# NIR-Spec-Motherboard-SCH_SH3__02.net
KiCad netlist of a schematic drawn in Altium Designer
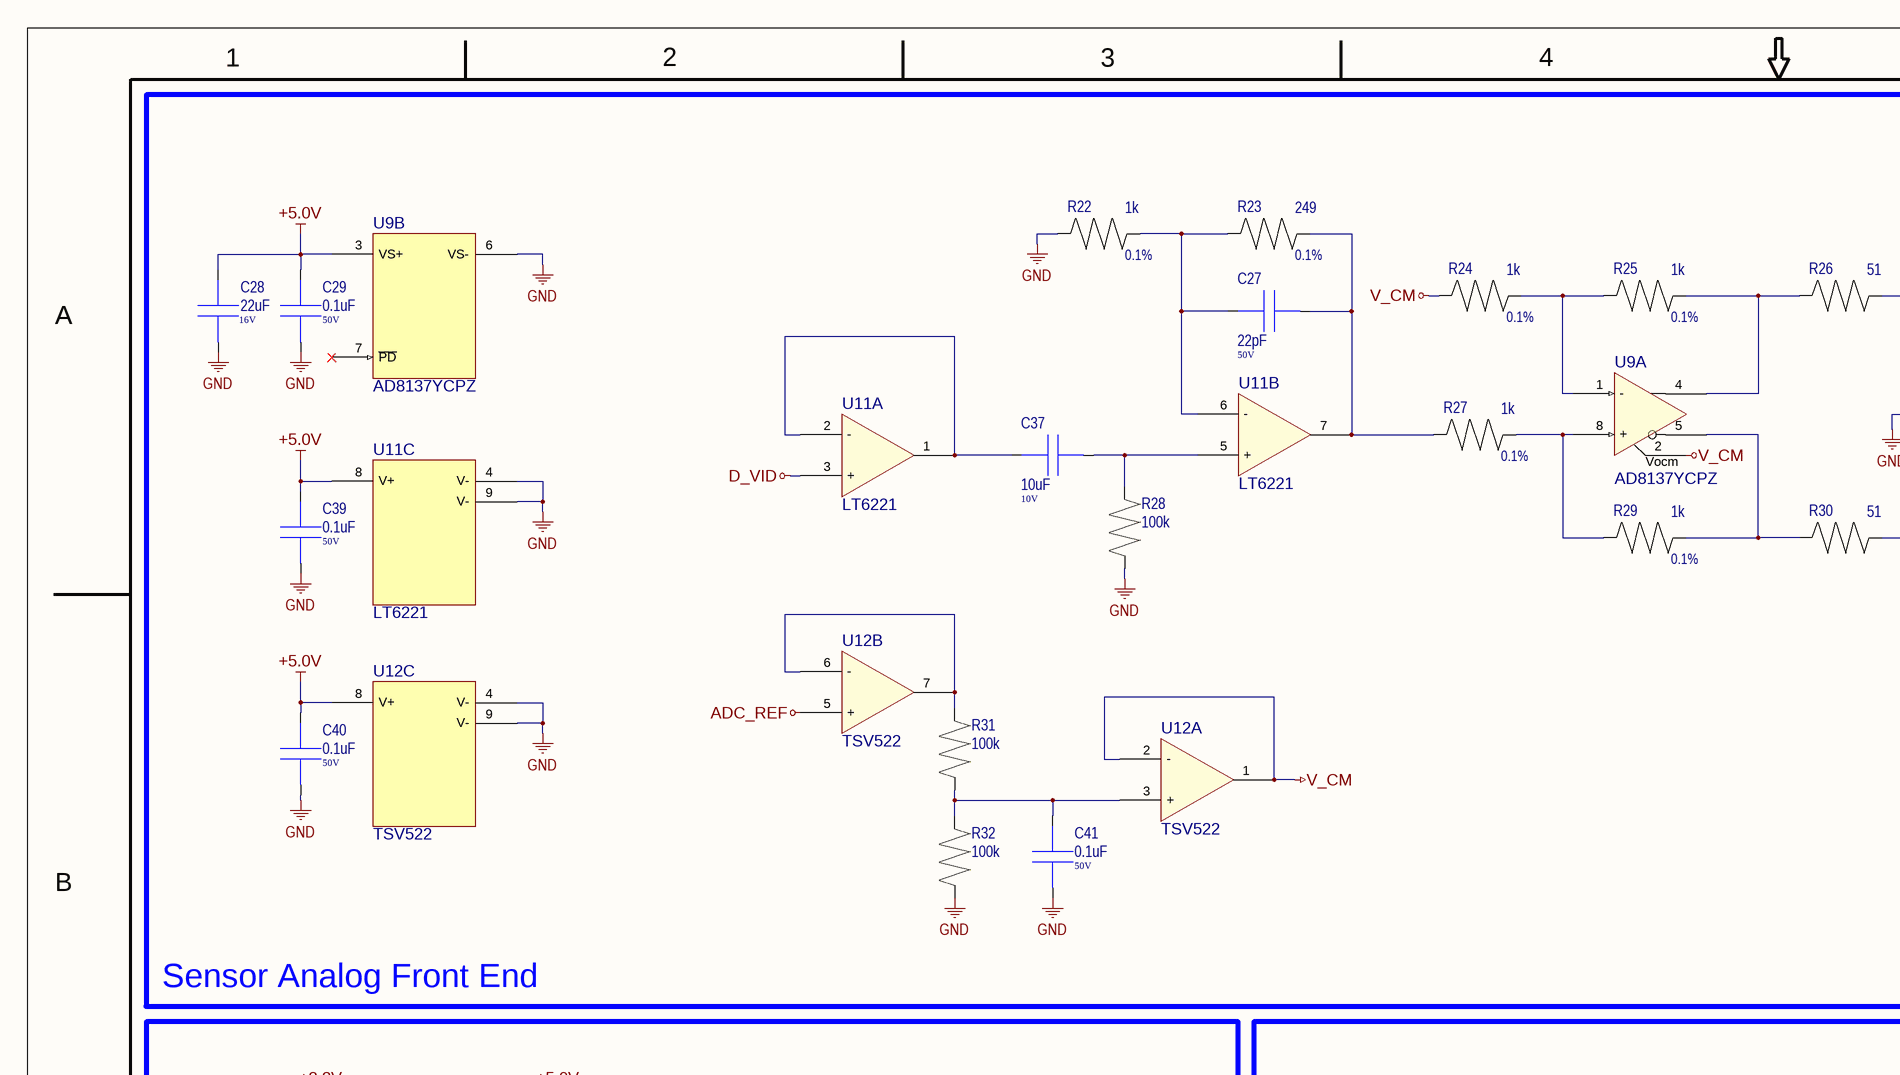
[diagram p0: NIR-Spec-Motherboard-SCH_SH3_(02).SchDoc, top left]
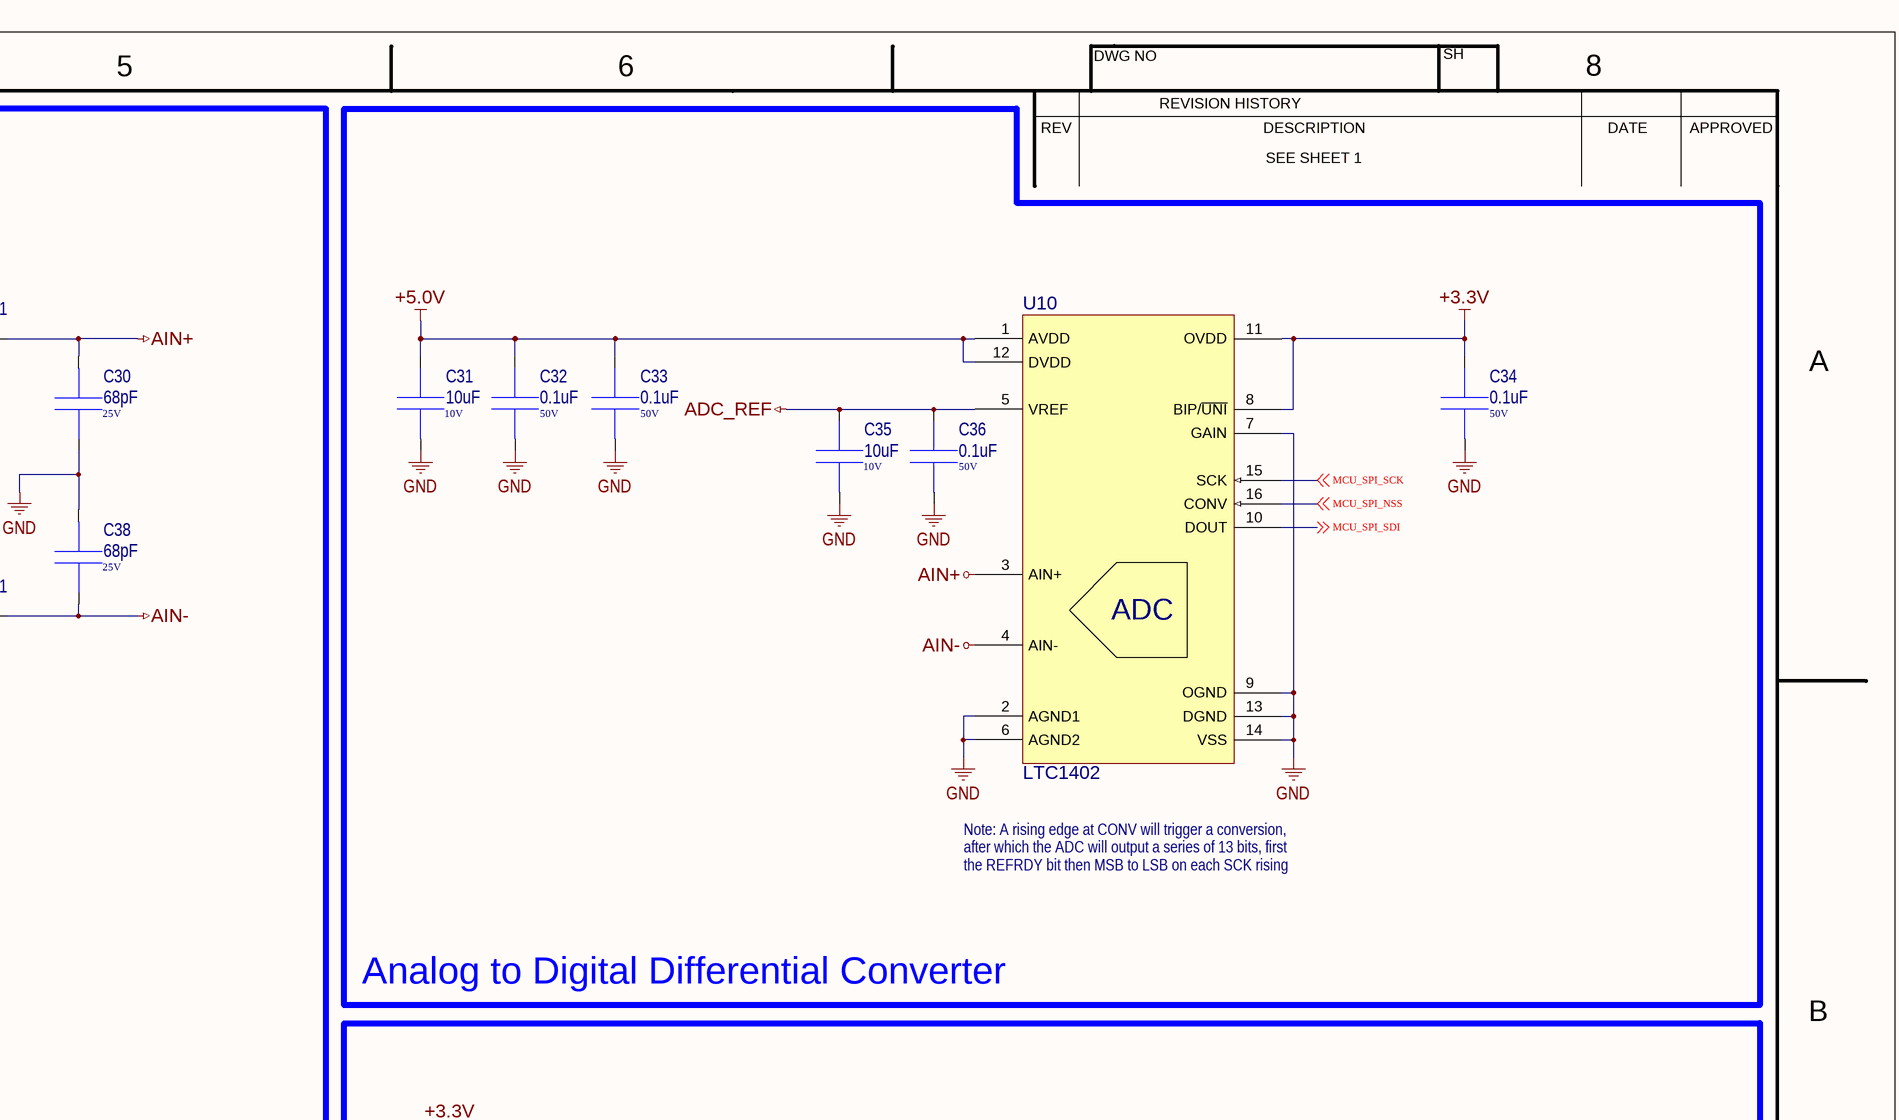
[diagram p1: NIR-Spec-Motherboard-SCH_SH3_(02).SchDoc, top right]
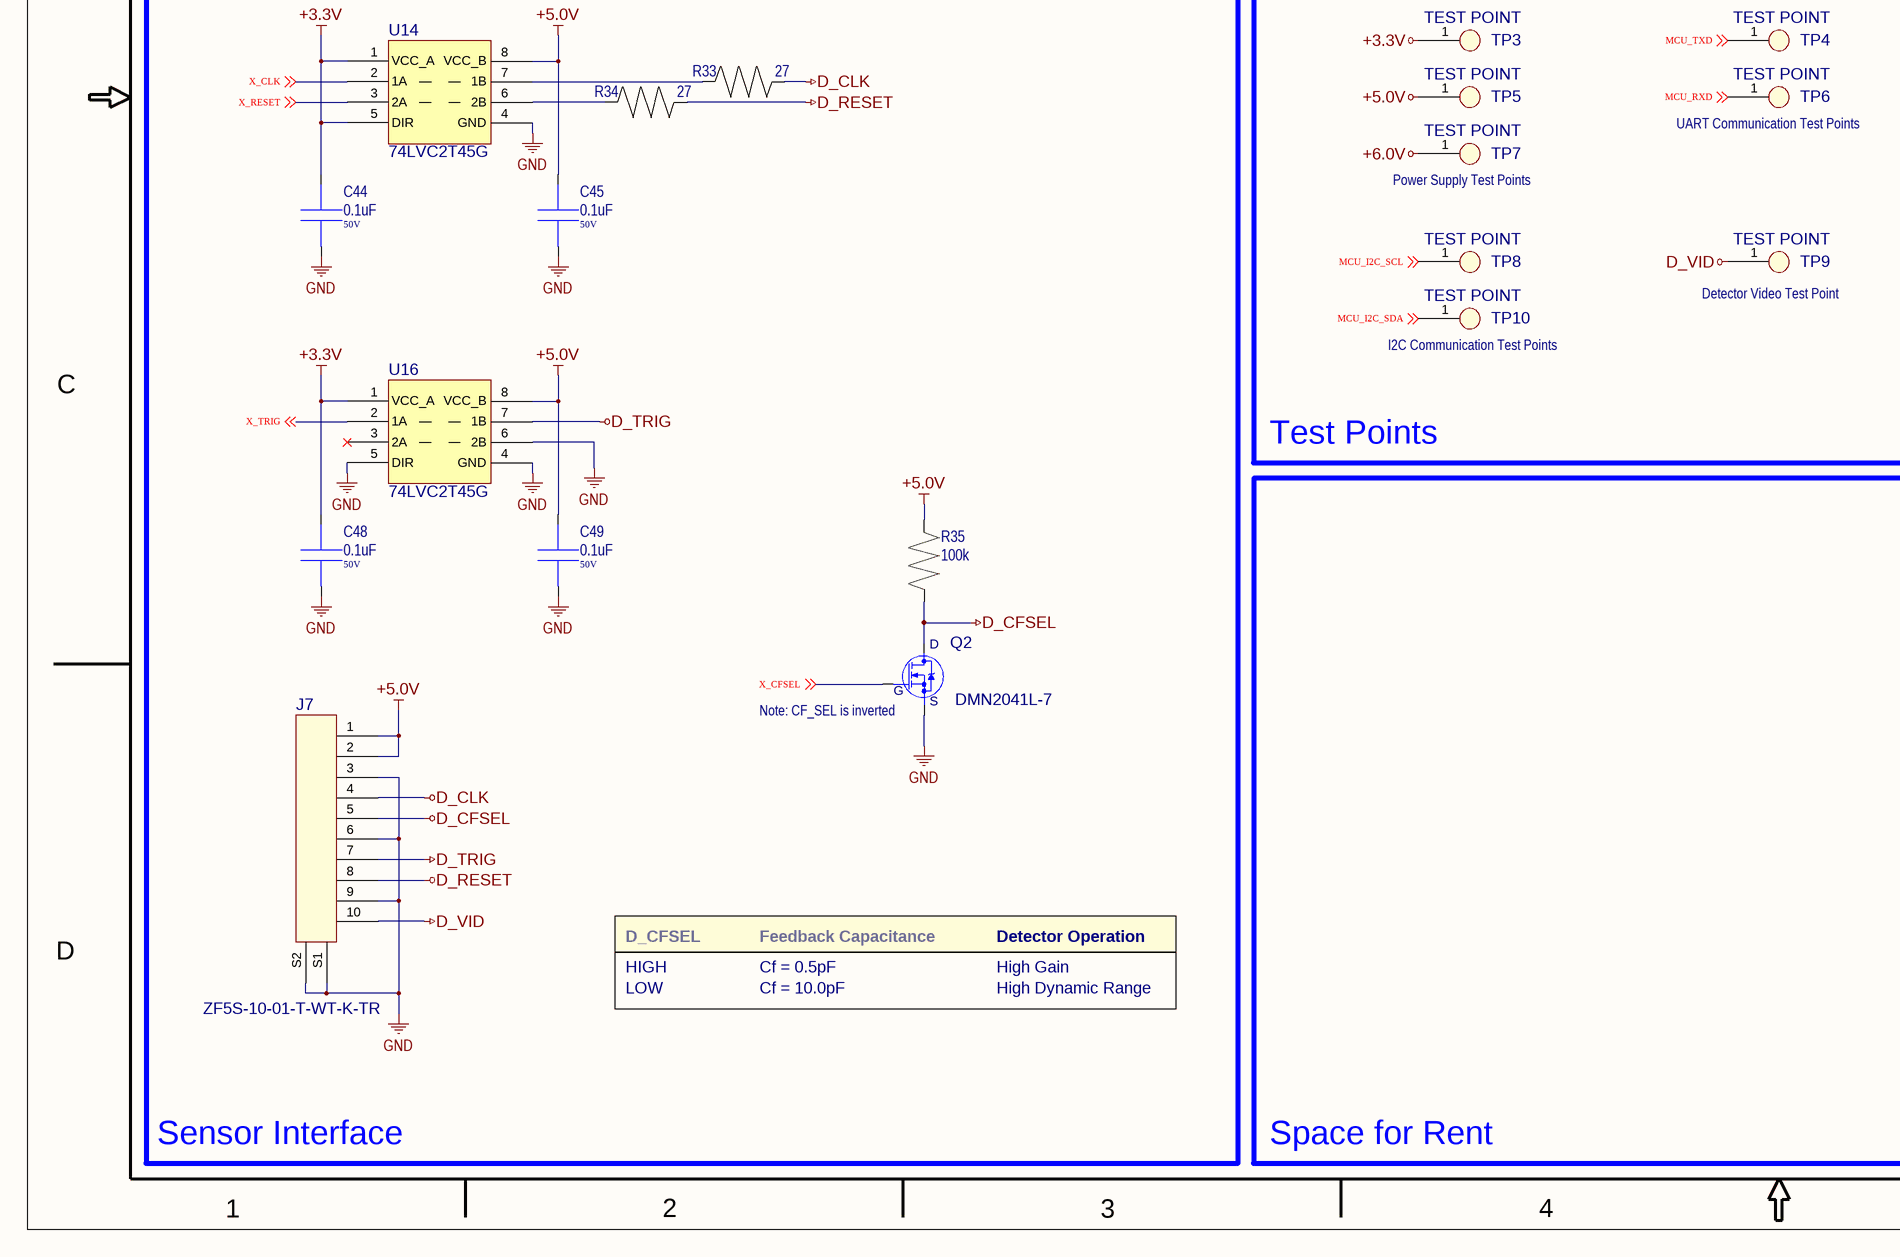
[diagram p2: NIR-Spec-Motherboard-SCH_SH3_(02).SchDoc, bottom left]
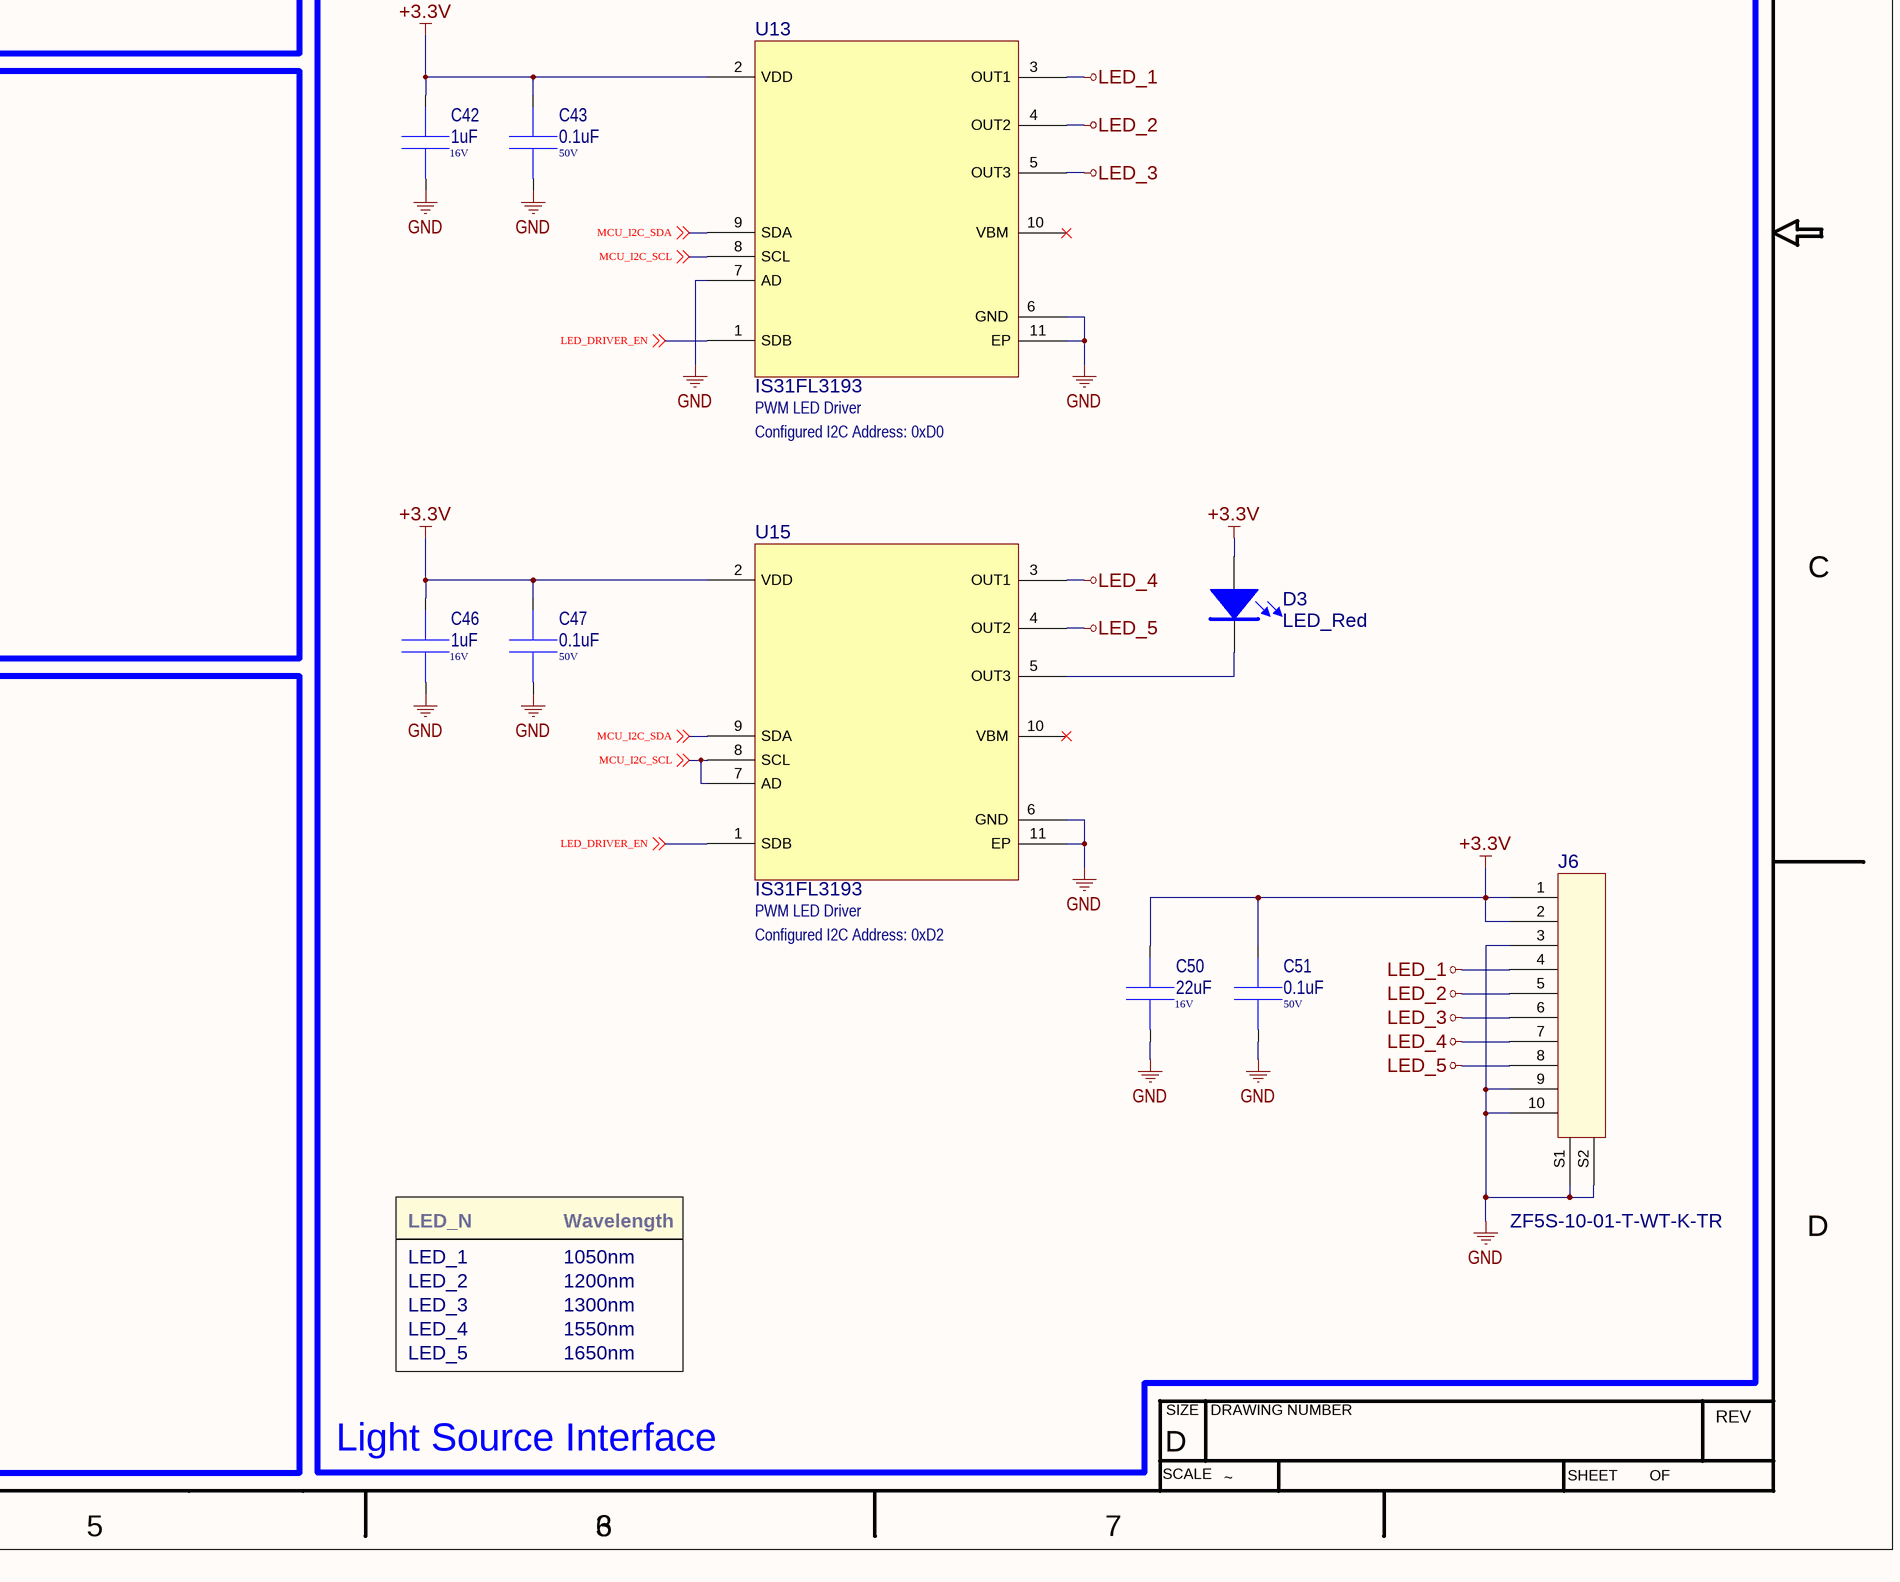
[diagram p3: NIR-Spec-Motherboard-SCH_SH3_(02).SchDoc, bottom right]

(export (version "E")
  (design (tool "Eeschema 10.0.6"))
  (components
    (comp (ref "C27")
      (value "22pF")
      (footprint "0603")
      (description "CAP CER 22PF NP0 50V 0603")
      (fields
        (field (name "PART NUMBER") "VJ0603A220KXAAC")
        (field (name "MANUFACTURER") "Vishay")
        (field (name "VOLTAGE") "50V")
      )
      (libsource (lib "CAPACITORS") (part "CAP"))
    )
    (comp (ref "C28")
      (value "22uF")
      (footprint "0805")
      (description "CAP CER 22UF 16V X5R 0805")
      (fields
        (field (name "PART NUMBER") "CL21A226MOCLRNC")
        (field (name "MANUFACTURER") "Samsung Electro-Mechanics")
        (field (name "VOLTAGE") "16V")
      )
      (libsource (lib "CAPACITORS") (part "CAP"))
    )
    (comp (ref "C29")
      (value "0.1uF")
      (footprint "0603")
      (description "CAP CER 0.1UF 50V X7R 0603")
      (fields
        (field (name "PART NUMBER") "C0603C104K5RAC3121")
        (field (name "MANUFACTURER") "KEMET")
        (field (name "VOLTAGE") "50V")
      )
      (libsource (lib "CAPACITORS") (part "CAP"))
    )
    (comp (ref "C30")
      (value "68pF")
      (footprint "0603")
      (description "CAP CER 68PF 25V NP0 0603")
      (fields
        (field (name "PART NUMBER") "VJ0603A680KXXPW1BC")
        (field (name "MANUFACTURER") "Vishay")
        (field (name "VOLTAGE") "25V")
      )
      (libsource (lib "CAPACITORS") (part "CAP"))
    )
    (comp (ref "C31")
      (value "10uF")
      (footprint "0603")
      (description "CAP CER 10UF 10V X6S 0603")
      (fields
        (field (name "PART NUMBER") "GRM188C81A106MA73D")
        (field (name "MANUFACTURER") "Murata Electronics")
        (field (name "VOLTAGE") "10V")
      )
      (libsource (lib "CAPACITORS") (part "CAP"))
    )
    (comp (ref "C32")
      (value "0.1uF")
      (footprint "0603")
      (description "CAP CER 0.1UF 50V X7R 0603")
      (fields
        (field (name "PART NUMBER") "C0603C104K5RAC3121")
        (field (name "MANUFACTURER") "KEMET")
        (field (name "VOLTAGE") "50V")
      )
      (libsource (lib "CAPACITORS") (part "CAP"))
    )
    (comp (ref "C33")
      (value "0.1uF")
      (footprint "0603")
      (description "CAP CER 0.1UF 50V X7R 0603")
      (fields
        (field (name "PART NUMBER") "C0603C104K5RAC3121")
        (field (name "MANUFACTURER") "KEMET")
        (field (name "VOLTAGE") "50V")
      )
      (libsource (lib "CAPACITORS") (part "CAP"))
    )
    (comp (ref "C34")
      (value "0.1uF")
      (footprint "0603")
      (description "CAP CER 0.1UF 50V X7R 0603")
      (fields
        (field (name "PART NUMBER") "C0603C104K5RAC3121")
        (field (name "MANUFACTURER") "KEMET")
        (field (name "VOLTAGE") "50V")
      )
      (libsource (lib "CAPACITORS") (part "CAP"))
    )
    (comp (ref "C35")
      (value "10uF")
      (footprint "0603")
      (description "CAP CER 10UF 10V X6S 0603")
      (fields
        (field (name "PART NUMBER") "GRM188C81A106MA73D")
        (field (name "MANUFACTURER") "Murata Electronics")
        (field (name "VOLTAGE") "10V")
      )
      (libsource (lib "CAPACITORS") (part "CAP"))
    )
    (comp (ref "C36")
      (value "0.1uF")
      (footprint "0603")
      (description "CAP CER 0.1UF 50V X7R 0603")
      (fields
        (field (name "PART NUMBER") "C0603C104K5RAC3121")
        (field (name "MANUFACTURER") "KEMET")
        (field (name "VOLTAGE") "50V")
      )
      (libsource (lib "CAPACITORS") (part "CAP"))
    )
    (comp (ref "C37")
      (value "10uF")
      (footprint "0603")
      (description "CAP CER 10UF 10V X6S 0603")
      (fields
        (field (name "PART NUMBER") "GRM188C81A106MA73D")
        (field (name "MANUFACTURER") "Murata Electronics")
        (field (name "VOLTAGE") "10V")
      )
      (libsource (lib "CAPACITORS") (part "CAP"))
    )
    (comp (ref "C38")
      (value "68pF")
      (footprint "0603")
      (description "CAP CER 68PF 25V NP0 0603")
      (fields
        (field (name "PART NUMBER") "VJ0603A680KXXPW1BC")
        (field (name "MANUFACTURER") "Vishay")
        (field (name "VOLTAGE") "25V")
      )
      (libsource (lib "CAPACITORS") (part "CAP"))
    )
    (comp (ref "C39")
      (value "0.1uF")
      (footprint "0603")
      (description "CAP CER 0.1UF 50V X7R 0603")
      (fields
        (field (name "PART NUMBER") "C0603C104K5RAC3121")
        (field (name "MANUFACTURER") "KEMET")
        (field (name "VOLTAGE") "50V")
      )
      (libsource (lib "CAPACITORS") (part "CAP"))
    )
    (comp (ref "C40")
      (value "0.1uF")
      (footprint "0603")
      (description "CAP CER 0.1UF 50V X7R 0603")
      (fields
        (field (name "PART NUMBER") "C0603C104K5RAC3121")
        (field (name "MANUFACTURER") "KEMET")
        (field (name "VOLTAGE") "50V")
      )
      (libsource (lib "CAPACITORS") (part "CAP"))
    )
    (comp (ref "C41")
      (value "0.1uF")
      (footprint "0603")
      (description "CAP CER 0.1UF 50V X7R 0603")
      (fields
        (field (name "PART NUMBER") "C0603C104K5RAC3121")
        (field (name "MANUFACTURER") "KEMET")
        (field (name "VOLTAGE") "50V")
      )
      (libsource (lib "CAPACITORS") (part "CAP"))
    )
    (comp (ref "C42")
      (value "1uF")
      (footprint "0603")
      (description "CAP CER 1UF 10V X5R 0603")
      (fields
        (field (name "PART NUMBER") "GRM188R61C105KA12J")
        (field (name "MANUFACTURER") "Murata Electronics")
        (field (name "VOLTAGE") "16V")
      )
      (libsource (lib "CAPACITORS") (part "CAP"))
    )
    (comp (ref "C43")
      (value "0.1uF")
      (footprint "0603")
      (description "CAP CER 0.1UF 50V X7R 0603")
      (fields
        (field (name "PART NUMBER") "C0603C104K5RAC3121")
        (field (name "MANUFACTURER") "KEMET")
        (field (name "VOLTAGE") "50V")
      )
      (libsource (lib "CAPACITORS") (part "CAP"))
    )
    (comp (ref "C44")
      (value "0.1uF")
      (footprint "0603")
      (description "CAP CER 0.1UF 50V X7R 0603")
      (fields
        (field (name "PART NUMBER") "C0603C104K5RAC3121")
        (field (name "MANUFACTURER") "KEMET")
        (field (name "VOLTAGE") "50V")
      )
      (libsource (lib "CAPACITORS") (part "CAP"))
    )
    (comp (ref "C45")
      (value "0.1uF")
      (footprint "0603")
      (description "CAP CER 0.1UF 50V X7R 0603")
      (fields
        (field (name "PART NUMBER") "C0603C104K5RAC3121")
        (field (name "MANUFACTURER") "KEMET")
        (field (name "VOLTAGE") "50V")
      )
      (libsource (lib "CAPACITORS") (part "CAP"))
    )
    (comp (ref "C46")
      (value "1uF")
      (footprint "0603")
      (description "CAP CER 1UF 10V X5R 0603")
      (fields
        (field (name "PART NUMBER") "GRM188R61C105KA12J")
        (field (name "MANUFACTURER") "Murata Electronics")
        (field (name "VOLTAGE") "16V")
      )
      (libsource (lib "CAPACITORS") (part "CAP"))
    )
    (comp (ref "C47")
      (value "0.1uF")
      (footprint "0603")
      (description "CAP CER 0.1UF 50V X7R 0603")
      (fields
        (field (name "PART NUMBER") "C0603C104K5RAC3121")
        (field (name "MANUFACTURER") "KEMET")
        (field (name "VOLTAGE") "50V")
      )
      (libsource (lib "CAPACITORS") (part "CAP"))
    )
    (comp (ref "C48")
      (value "0.1uF")
      (footprint "0603")
      (description "CAP CER 0.1UF 50V X7R 0603")
      (fields
        (field (name "PART NUMBER") "C0603C104K5RAC3121")
        (field (name "MANUFACTURER") "KEMET")
        (field (name "VOLTAGE") "50V")
      )
      (libsource (lib "CAPACITORS") (part "CAP"))
    )
    (comp (ref "C49")
      (value "0.1uF")
      (footprint "0603")
      (description "CAP CER 0.1UF 50V X7R 0603")
      (fields
        (field (name "PART NUMBER") "C0603C104K5RAC3121")
        (field (name "MANUFACTURER") "KEMET")
        (field (name "VOLTAGE") "50V")
      )
      (libsource (lib "CAPACITORS") (part "CAP"))
    )
    (comp (ref "C50")
      (value "22uF")
      (footprint "0805")
      (description "CAP CER 22UF 16V X5R 0805")
      (fields
        (field (name "PART NUMBER") "CL21A226MOCLRNC")
        (field (name "MANUFACTURER") "Samsung Electro-Mechanics")
        (field (name "VOLTAGE") "16V")
      )
      (libsource (lib "CAPACITORS") (part "CAP"))
    )
    (comp (ref "C51")
      (value "0.1uF")
      (footprint "0603")
      (description "CAP CER 0.1UF 50V X7R 0603")
      (fields
        (field (name "PART NUMBER") "C0603C104K5RAC3121")
        (field (name "MANUFACTURER") "KEMET")
        (field (name "VOLTAGE") "50V")
      )
      (libsource (lib "CAPACITORS") (part "CAP"))
    )
    (comp (ref "D3")
      (value "LED_Red")
      (footprint "0603_LED_Red")
      (description "Standard LEDs - SMD HE Red 645 nm Water Clear")
      (fields (field (name "PART NUMBER") "SM0603HCL") (field (name "MANUFACTURER") "Bivar"))
      (libsource (lib "SEMICONDUCTORS") (part "LED_Red"))
    )
    (comp (ref "J6")
      (value "ZF5S-10-01-T-WT-K-TR")
      (footprint "ZF5S-10-01-T-WT-K-TR")
      (fields (field (name "MANUFACTURER") "Samtec"))
      (libsource (lib "ZF5S-10-01-T-WT-K-TR") (part "ZF5S-10-01-T-WT-K-TR"))
    )
    (comp (ref "J7")
      (value "ZF5S-10-01-T-WT-K-TR")
      (footprint "ZF5S-10-01-T-WT-K-TR")
      (fields (field (name "MANUFACTURER") "Samtec"))
      (libsource (lib "") (part "ZF5S-10-01-T-WT-K-TR_1"))
    )
    (comp (ref "Q2")
      (value "DMN2041L-7")
      (footprint "SOT-23")
      (description "MOSFET, N CH, 3-PIN")
      (fields (field (name "MANUFACTURER") "Diodes Incorporated"))
      (libsource (lib "SEMICONDUCTORS") (part "MOSFET_N"))
    )
    (comp (ref "R22")
      (value "1k")
      (footprint "0603")
      (description "Thin Film Resistors - SMD CPF A 0603 1K0 0.1% 25PPM")
      (fields (field (name "PART NUMBER") "CPF-A-0603B1K0E") (field (name "MANUFACTURER") "TE Connectivity"))
      (libsource (lib "RESISTORS") (part "RES"))
    )
    (comp (ref "R23")
      (value "249")
      (footprint "0603")
      (description "Thin Film Resistors - SMD 0603 249ohms 25ppm 0.5%")
      (fields (field (name "PART NUMBER") "ERA-3AED2490V") (field (name "MANUFACTURER") "Panasonic"))
      (libsource (lib "RESISTORS") (part "RES"))
    )
    (comp (ref "R24")
      (value "1k")
      (footprint "0603")
      (description "Thin Film Resistors - SMD CPF A 0603 1K0 0.1% 25PPM")
      (fields (field (name "PART NUMBER") "CPF-A-0603B1K0E") (field (name "MANUFACTURER") "TE Connectivity"))
      (libsource (lib "RESISTORS") (part "RES"))
    )
    (comp (ref "R25")
      (value "1k")
      (footprint "0603")
      (description "Thin Film Resistors - SMD CPF A 0603 1K0 0.1% 25PPM")
      (fields (field (name "PART NUMBER") "CPF-A-0603B1K0E") (field (name "MANUFACTURER") "TE Connectivity"))
      (libsource (lib "RESISTORS") (part "RES"))
    )
    (comp (ref "R26")
      (value "51")
      (footprint "0603")
      (description "Thin Film Resistors - SMD .1W 51ohm 1% 0603")
      (fields (field (name "PART NUMBER") "MCT06030C5109FP500") (field (name "MANUFACTURER") "Vishay"))
      (libsource (lib "RESISTORS") (part "RES"))
    )
    (comp (ref "R27")
      (value "1k")
      (footprint "0603")
      (description "Thin Film Resistors - SMD CPF A 0603 1K0 0.1% 25PPM")
      (fields (field (name "PART NUMBER") "CPF-A-0603B1K0E") (field (name "MANUFACTURER") "TE Connectivity"))
      (libsource (lib "RESISTORS") (part "RES"))
    )
    (comp (ref "R28")
      (value "100k")
      (footprint "0603")
      (description "Thick Film Resistors - SMD 0.33W 100Kohms 5%")
      (fields (field (name "PART NUMBER") "CRCW0603100KJNEAHP") (field (name "MANUFACTURER") "Vishay"))
      (libsource (lib "RESISTORS") (part "RES"))
    )
    (comp (ref "R29")
      (value "1k")
      (footprint "0603")
      (description "Thin Film Resistors - SMD CPF A 0603 1K0 0.1% 25PPM")
      (fields (field (name "PART NUMBER") "CPF-A-0603B1K0E") (field (name "MANUFACTURER") "TE Connectivity"))
      (libsource (lib "RESISTORS") (part "RES"))
    )
    (comp (ref "R30")
      (value "51")
      (footprint "0603")
      (description "Thin Film Resistors - SMD .1W 51ohm 1% 0603")
      (fields (field (name "PART NUMBER") "MCT06030C5109FP500") (field (name "MANUFACTURER") "Vishay"))
      (libsource (lib "RESISTORS") (part "RES"))
    )
    (comp (ref "R31")
      (value "100k")
      (footprint "0603")
      (description "Thick Film Resistors - SMD 0.33W 100Kohms 5%")
      (fields (field (name "PART NUMBER") "CRCW0603100KJNEAHP") (field (name "MANUFACTURER") "Vishay"))
      (libsource (lib "RESISTORS") (part "RES"))
    )
    (comp (ref "R32")
      (value "100k")
      (footprint "0603")
      (description "Thick Film Resistors - SMD 0.33W 100Kohms 5%")
      (fields (field (name "PART NUMBER") "CRCW0603100KJNEAHP") (field (name "MANUFACTURER") "Vishay"))
      (libsource (lib "RESISTORS") (part "RES"))
    )
    (comp (ref "R33")
      (value "27")
      (footprint "0603")
      (description "Thin Film Resistors - SMD 0603 27ohms 50ppm 0.5%")
      (fields (field (name "PART NUMBER") "ERA-3AHD270V") (field (name "MANUFACTURER") "Panasonic"))
      (libsource (lib "RESISTORS") (part "RES"))
    )
    (comp (ref "R34")
      (value "27")
      (footprint "0603")
      (description "Thin Film Resistors - SMD 0603 27ohms 50ppm 0.5%")
      (fields (field (name "PART NUMBER") "ERA-3AHD270V") (field (name "MANUFACTURER") "Panasonic"))
      (libsource (lib "RESISTORS") (part "RES"))
    )
    (comp (ref "R35")
      (value "100k")
      (footprint "0603")
      (description "Thick Film Resistors - SMD 0.33W 100Kohms 5%")
      (fields (field (name "PART NUMBER") "CRCW0603100KJNEAHP") (field (name "MANUFACTURER") "Vishay"))
      (libsource (lib "RESISTORS") (part "RES"))
    )
    (comp (ref "TP3")
      (value "TEST POINT")
      (footprint "30x40 TP")
      (libsource (lib "TestPoint") (part "TEST POINT"))
    )
    (comp (ref "TP4")
      (value "TEST POINT")
      (footprint "30x40 TP")
      (libsource (lib "TestPoint") (part "TEST POINT"))
    )
    (comp (ref "TP5")
      (value "TEST POINT")
      (footprint "30x40 TP")
      (libsource (lib "TestPoint") (part "TEST POINT"))
    )
    (comp (ref "TP6")
      (value "TEST POINT")
      (footprint "30x40 TP")
      (libsource (lib "TestPoint") (part "TEST POINT"))
    )
    (comp (ref "TP7")
      (value "TEST POINT")
      (footprint "30x40 TP")
      (libsource (lib "TestPoint") (part "TEST POINT"))
    )
    (comp (ref "TP8")
      (value "TEST POINT")
      (footprint "30x40 TP")
      (libsource (lib "TestPoint") (part "TEST POINT"))
    )
    (comp (ref "TP9")
      (value "TEST POINT")
      (footprint "30x40 TP")
      (libsource (lib "TestPoint") (part "TEST POINT"))
    )
    (comp (ref "TP10")
      (value "TEST POINT")
      (footprint "30x40 TP")
      (libsource (lib "TestPoint") (part "TEST POINT"))
    )
    (comp (ref "U9")
      (value "AD8137YCPZ")
      (footprint "SOIC_8")
      (description "IC OPAMP DIFF 110MHZ RRO 8SOIC")
      (fields (field (name "MANUFACTURER") "Analog Devices"))
      (libsource (lib "Op_Amps") (part "AD8137YRZ-Rxxxx"))
    )
    (comp (ref "U10")
      (value "LTC1402")
      (footprint "LTC1402")
      (description "12 Bit Analog to Digital Converter 1 Input 1 SAR 16-SSOP")
      (fields (field (name "MANUFACTURER") "Linear Technology"))
      (libsource (lib "LTC1402") (part "LTC1402"))
    )
    (comp (ref "U11")
      (value "LT6221")
      (footprint "DFN-8(3x3)")
      (description "IC OPAMP GP 2 CIRCUIT 8DFN")
      (fields
        (field (name "MANUFACTURER") "Linear Technology")
        (field (name "PART NUMBER") "LT6221xDD#TRPBF")
      )
      (libsource (lib "Op_Amps") (part "LT6221xDD#TRPBF"))
    )
    (comp (ref "U12")
      (value "TSV522")
      (footprint "DFN-8 2x2")
      (description "IC CMOS 2 CIRCUIT 8DFN")
      (fields (field (name "MANUFACTURER") "ST Microelectronics") (field (name "PART NUMBER") "TSV522IQ2T"))
      (libsource (lib "TSV522") (part "TSV522"))
    )
    (comp (ref "U13")
      (value "IS31FL3193")
      (footprint "DFN-10")
      (description "IC LED DRIVER LINEAR 42MA 10DFN")
      (fields
        (field (name "MANUFACTURER") "Lumissil Microsystems")
        (field (name "PART NUMBER") "IS31FL3193-DLS2-TR")
      )
      (libsource (lib "IS31FL3193") (part "IS31FL3193"))
    )
    (comp (ref "U14")
      (value "74LVC2T45G")
      (footprint "SOT-765")
      (description "IC TRNSLTR BIDIRECTIONAL 8XSON")
      (fields (field (name "MANUFACTURER") "Nexperia USA") (field (name "PART NUMBER") "74LVC2T45DC,115"))
      (libsource (lib "Logic") (part "74LVC2T45G"))
    )
    (comp (ref "U15")
      (value "IS31FL3193")
      (footprint "DFN-10")
      (description "IC LED DRIVER LINEAR 42MA 10DFN")
      (fields
        (field (name "MANUFACTURER") "Lumissil Microsystems")
        (field (name "PART NUMBER") "IS31FL3193-DLS2-TR")
      )
      (libsource (lib "IS31FL3193") (part "IS31FL3193"))
    )
    (comp (ref "U16")
      (value "74LVC2T45G")
      (footprint "SOT-765")
      (description "IC TRNSLTR BIDIRECTIONAL 8XSON")
      (fields (field (name "MANUFACTURER") "Nexperia USA") (field (name "PART NUMBER") "74LVC2T45DC,115"))
      (libsource (lib "Logic") (part "74LVC2T45G"))
    )
  )
  (nets
    (net (code "1") (name "+3.3V") (class "Default")
      (node (ref "C34") (pin "2") (pinfunction "2_2") (pintype "passive"))
      (node (ref "C42") (pin "2") (pinfunction "2_2") (pintype "passive"))
      (node (ref "C43") (pin "2") (pinfunction "2_2") (pintype "passive"))
      (node (ref "C44") (pin "2") (pinfunction "2_2") (pintype "passive"))
      (node (ref "C46") (pin "2") (pinfunction "2_2") (pintype "passive"))
      (node (ref "C47") (pin "2") (pinfunction "2_2") (pintype "passive"))
      (node (ref "C48") (pin "2") (pinfunction "2_2") (pintype "passive"))
      (node (ref "C50") (pin "2") (pinfunction "2_2") (pintype "passive"))
      (node (ref "C51") (pin "2") (pinfunction "2_2") (pintype "passive"))
      (node (ref "D3") (pin "1") (pinfunction "A_1") (pintype "passive"))
      (node (ref "J6") (pin "1") (pinfunction "1_1") (pintype "passive"))
      (node (ref "J6") (pin "2") (pinfunction "2_2") (pintype "passive"))
      (node (ref "TP3") (pin "1") (pinfunction "1_1") (pintype "passive"))
      (node (ref "U10") (pin "11") (pinfunction "OVDD_11") (pintype "power_in"))
      (node (ref "U10") (pin "8") (pinfunction "BIP/~{UNI}_8") (pintype "passive"))
      (node (ref "U13") (pin "2") (pinfunction "VDD_2") (pintype "passive"))
      (node (ref "U14") (pin "1") (pinfunction "VCC_A_1") (pintype "passive"))
      (node (ref "U14") (pin "5") (pinfunction "DIR_5") (pintype "power_in"))
      (node (ref "U15") (pin "2") (pinfunction "VDD_2") (pintype "passive"))
      (node (ref "U16") (pin "1") (pinfunction "VCC_A_1") (pintype "passive"))
    )
    (net (code "2") (name "+5.0V") (class "Default")
      (node (ref "C28") (pin "2") (pinfunction "2_2") (pintype "passive"))
      (node (ref "C29") (pin "2") (pinfunction "2_2") (pintype "passive"))
      (node (ref "C31") (pin "2") (pinfunction "2_2") (pintype "passive"))
      (node (ref "C32") (pin "2") (pinfunction "2_2") (pintype "passive"))
      (node (ref "C33") (pin "2") (pinfunction "2_2") (pintype "passive"))
      (node (ref "C39") (pin "2") (pinfunction "2_2") (pintype "passive"))
      (node (ref "C40") (pin "2") (pinfunction "2_2") (pintype "passive"))
      (node (ref "C45") (pin "2") (pinfunction "2_2") (pintype "passive"))
      (node (ref "C49") (pin "2") (pinfunction "2_2") (pintype "passive"))
      (node (ref "J7") (pin "1") (pinfunction "1_1") (pintype "passive"))
      (node (ref "J7") (pin "2") (pinfunction "2_2") (pintype "passive"))
      (node (ref "R35") (pin "1") (pinfunction "1_1") (pintype "passive"))
      (node (ref "TP5") (pin "1") (pinfunction "1_1") (pintype "passive"))
      (node (ref "U10") (pin "1") (pinfunction "AVDD_1") (pintype "passive"))
      (node (ref "U10") (pin "12") (pinfunction "DVDD_12") (pintype "power_in"))
      (node (ref "U11") (pin "8") (pinfunction "V+_8") (pintype "power_in"))
      (node (ref "U12") (pin "8") (pinfunction "V+_8") (pintype "power_in"))
      (node (ref "U14") (pin "8") (pinfunction "VCC_B_8") (pintype "power_in"))
      (node (ref "U16") (pin "8") (pinfunction "VCC_B_8") (pintype "power_in"))
      (node (ref "U9") (pin "3") (pinfunction "VS+_3") (pintype "power_in"))
    )
    (net (code "3") (name "+6.0V") (class "Default")
      (node (ref "TP7") (pin "1") (pinfunction "1_1") (pintype "passive"))
    )
    (net (code "4") (name "ADC_REF") (class "Default")
      (node (ref "C35") (pin "2") (pinfunction "2_2") (pintype "passive"))
      (node (ref "C36") (pin "2") (pinfunction "2_2") (pintype "passive"))
      (node (ref "U10") (pin "5") (pinfunction "VREF_5") (pintype "passive"))
      (node (ref "U12") (pin "5") (pinfunction "+_5") (pintype "passive"))
    )
    (net (code "5") (name "AIN+") (class "Default")
      (node (ref "C30") (pin "1") (pinfunction "1_1") (pintype "passive"))
      (node (ref "R26") (pin "2") (pinfunction "2_2") (pintype "passive"))
      (node (ref "U10") (pin "3") (pinfunction "AIN+_3") (pintype "passive"))
    )
    (net (code "6") (name "AIN-") (class "Default")
      (node (ref "C38") (pin "2") (pinfunction "2_2") (pintype "passive"))
      (node (ref "R30") (pin "2") (pinfunction "2_2") (pintype "passive"))
      (node (ref "U10") (pin "4") (pinfunction "AIN-_4") (pintype "power_in"))
    )
    (net (code "7") (name "D_CFSEL") (class "Default")
      (node (ref "J7") (pin "5") (pinfunction "5_5") (pintype "passive"))
      (node (ref "Q2") (pin "2") (pinfunction "D_2") (pintype "passive"))
      (node (ref "R35") (pin "2") (pinfunction "2_2") (pintype "passive"))
    )
    (net (code "8") (name "D_CLK") (class "Default")
      (node (ref "J7") (pin "4") (pinfunction "4_4") (pintype "passive"))
      (node (ref "R33") (pin "2") (pinfunction "2_2") (pintype "passive"))
    )
    (net (code "9") (name "D_RESET") (class "Default")
      (node (ref "J7") (pin "8") (pinfunction "8_8") (pintype "passive"))
      (node (ref "R34") (pin "2") (pinfunction "2_2") (pintype "passive"))
    )
    (net (code "10") (name "D_TRIG") (class "Default")
      (node (ref "J7") (pin "7") (pinfunction "7_7") (pintype "passive"))
      (node (ref "U16") (pin "7") (pinfunction "1B_7") (pintype "passive"))
    )
    (net (code "11") (name "D_VID") (class "Default")
      (node (ref "J7") (pin "10") (pinfunction "10_10") (pintype "passive"))
      (node (ref "TP9") (pin "1") (pinfunction "1_1") (pintype "passive"))
      (node (ref "U11") (pin "3") (pinfunction "+_3") (pintype "passive"))
    )
    (net (code "12") (name "GND") (class "Default")
      (node (ref "C28") (pin "1") (pinfunction "1_1") (pintype "passive"))
      (node (ref "C29") (pin "1") (pinfunction "1_1") (pintype "passive"))
      (node (ref "C30") (pin "2") (pinfunction "2_2") (pintype "passive"))
      (node (ref "C31") (pin "1") (pinfunction "1_1") (pintype "passive"))
      (node (ref "C32") (pin "1") (pinfunction "1_1") (pintype "passive"))
      (node (ref "C33") (pin "1") (pinfunction "1_1") (pintype "passive"))
      (node (ref "C34") (pin "1") (pinfunction "1_1") (pintype "passive"))
      (node (ref "C35") (pin "1") (pinfunction "1_1") (pintype "passive"))
      (node (ref "C36") (pin "1") (pinfunction "1_1") (pintype "passive"))
      (node (ref "C38") (pin "1") (pinfunction "1_1") (pintype "passive"))
      (node (ref "C39") (pin "1") (pinfunction "1_1") (pintype "passive"))
      (node (ref "C40") (pin "1") (pinfunction "1_1") (pintype "passive"))
      (node (ref "C41") (pin "1") (pinfunction "1_1") (pintype "passive"))
      (node (ref "C42") (pin "1") (pinfunction "1_1") (pintype "passive"))
      (node (ref "C43") (pin "1") (pinfunction "1_1") (pintype "passive"))
      (node (ref "C44") (pin "1") (pinfunction "1_1") (pintype "passive"))
      (node (ref "C45") (pin "1") (pinfunction "1_1") (pintype "passive"))
      (node (ref "C46") (pin "1") (pinfunction "1_1") (pintype "passive"))
      (node (ref "C47") (pin "1") (pinfunction "1_1") (pintype "passive"))
      (node (ref "C48") (pin "1") (pinfunction "1_1") (pintype "passive"))
      (node (ref "C49") (pin "1") (pinfunction "1_1") (pintype "passive"))
      (node (ref "C50") (pin "1") (pinfunction "1_1") (pintype "passive"))
      (node (ref "C51") (pin "1") (pinfunction "1_1") (pintype "passive"))
      (node (ref "J6") (pin "10") (pinfunction "10_10") (pintype "passive"))
      (node (ref "J6") (pin "3") (pinfunction "3_3") (pintype "passive"))
      (node (ref "J6") (pin "9") (pinfunction "9_9") (pintype "passive"))
      (node (ref "J6") (pin "S1") (pinfunction "S1_S1") (pintype "passive"))
      (node (ref "J6") (pin "S2") (pinfunction "S2_S2") (pintype "passive"))
      (node (ref "J7") (pin "3") (pinfunction "3_3") (pintype "passive"))
      (node (ref "J7") (pin "6") (pinfunction "6_6") (pintype "passive"))
      (node (ref "J7") (pin "9") (pinfunction "9_9") (pintype "passive"))
      (node (ref "J7") (pin "S1") (pinfunction "S1_S1") (pintype "passive"))
      (node (ref "J7") (pin "S2") (pinfunction "S2_S2") (pintype "passive"))
      (node (ref "Q2") (pin "3") (pinfunction "S_3") (pintype "passive"))
      (node (ref "R22") (pin "1") (pinfunction "1_1") (pintype "passive"))
      (node (ref "R28") (pin "2") (pinfunction "2_2") (pintype "passive"))
      (node (ref "R32") (pin "2") (pinfunction "2_2") (pintype "passive"))
      (node (ref "U10") (pin "13") (pinfunction "DGND_13") (pintype "power_in"))
      (node (ref "U10") (pin "14") (pinfunction "VSS_14") (pintype "power_in"))
      (node (ref "U10") (pin "2") (pinfunction "AGND1_2") (pintype "passive"))
      (node (ref "U10") (pin "6") (pinfunction "AGND2_6") (pintype "passive"))
      (node (ref "U10") (pin "7") (pinfunction "GAIN_7") (pintype "passive"))
      (node (ref "U10") (pin "9") (pinfunction "OGND_9") (pintype "power_in"))
      (node (ref "U11") (pin "4") (pinfunction "V-_4") (pintype "power_in"))
      (node (ref "U11") (pin "9") (pinfunction "V-_9") (pintype "power_in"))
      (node (ref "U12") (pin "4") (pinfunction "V-_4") (pintype "power_in"))
      (node (ref "U12") (pin "9") (pinfunction "V-_9") (pintype "power_in"))
      (node (ref "U13") (pin "11") (pinfunction "EP_11") (pintype "passive"))
      (node (ref "U13") (pin "6") (pinfunction "GND_6") (pintype "passive"))
      (node (ref "U13") (pin "7") (pinfunction "AD_7") (pintype "passive"))
      (node (ref "U14") (pin "4") (pinfunction "GND_4") (pintype "power_in"))
      (node (ref "U15") (pin "11") (pinfunction "EP_11") (pintype "passive"))
      (node (ref "U15") (pin "6") (pinfunction "GND_6") (pintype "passive"))
      (node (ref "U16") (pin "4") (pinfunction "GND_4") (pintype "power_in"))
      (node (ref "U16") (pin "5") (pinfunction "DIR_5") (pintype "power_in"))
      (node (ref "U16") (pin "6") (pinfunction "2B_6") (pintype "passive"))
      (node (ref "U9") (pin "6") (pinfunction "VS-_6") (pintype "power_in"))
    )
    (net (code "13") (name "LED_1") (class "Default")
      (node (ref "J6") (pin "4") (pinfunction "4_4") (pintype "passive"))
      (node (ref "U13") (pin "3") (pinfunction "OUT1_3") (pintype "passive"))
    )
    (net (code "14") (name "LED_2") (class "Default")
      (node (ref "J6") (pin "5") (pinfunction "5_5") (pintype "passive"))
      (node (ref "U13") (pin "4") (pinfunction "OUT2_4") (pintype "passive"))
    )
    (net (code "15") (name "LED_3") (class "Default")
      (node (ref "J6") (pin "6") (pinfunction "6_6") (pintype "passive"))
      (node (ref "U13") (pin "5") (pinfunction "OUT3_5") (pintype "passive"))
    )
    (net (code "16") (name "LED_4") (class "Default")
      (node (ref "J6") (pin "7") (pinfunction "7_7") (pintype "passive"))
      (node (ref "U15") (pin "3") (pinfunction "OUT1_3") (pintype "passive"))
    )
    (net (code "17") (name "LED_5") (class "Default")
      (node (ref "J6") (pin "8") (pinfunction "8_8") (pintype "passive"))
      (node (ref "U15") (pin "4") (pinfunction "OUT2_4") (pintype "passive"))
    )
    (net (code "18") (name "LED_DRIVER_EN") (class "Default")
      (node (ref "U13") (pin "1") (pinfunction "SDB_1") (pintype "passive"))
      (node (ref "U15") (pin "1") (pinfunction "SDB_1") (pintype "passive"))
    )
    (net (code "19") (name "MCU_I2C_SCL") (class "Default")
      (node (ref "TP8") (pin "1") (pinfunction "1_1") (pintype "passive"))
      (node (ref "U13") (pin "8") (pinfunction "SCL_8") (pintype "passive"))
      (node (ref "U15") (pin "7") (pinfunction "AD_7") (pintype "passive"))
      (node (ref "U15") (pin "8") (pinfunction "SCL_8") (pintype "passive"))
    )
    (net (code "20") (name "MCU_I2C_SDA") (class "Default")
      (node (ref "TP10") (pin "1") (pinfunction "1_1") (pintype "passive"))
      (node (ref "U13") (pin "9") (pinfunction "SDA_9") (pintype "passive"))
      (node (ref "U15") (pin "9") (pinfunction "SDA_9") (pintype "passive"))
    )
    (net (code "21") (name "MCU_RXD") (class "Default")
      (node (ref "TP6") (pin "1") (pinfunction "1_1") (pintype "passive"))
    )
    (net (code "22") (name "MCU_SPI_NSS") (class "Default")
      (node (ref "U10") (pin "16") (pinfunction "CONV_16") (pintype "input"))
    )
    (net (code "23") (name "MCU_SPI_SCK") (class "Default")
      (node (ref "U10") (pin "15") (pinfunction "SCK_15") (pintype "input"))
    )
    (net (code "24") (name "MCU_SPI_SDI") (class "Default")
      (node (ref "U10") (pin "10") (pinfunction "DOUT_10") (pintype "power_in"))
    )
    (net (code "25") (name "MCU_TXD") (class "Default")
      (node (ref "TP4") (pin "1") (pinfunction "1_1") (pintype "passive"))
    )
    (net (code "26") (name "Net-(D3-K)") (class "Default")
      (node (ref "D3") (pin "2") (pinfunction "K_2") (pintype "passive"))
      (node (ref "U15") (pin "5") (pinfunction "OUT3_5") (pintype "passive"))
    )
    (net (code "27") (name "Net-(U9A-+)") (class "Default")
      (node (ref "R27") (pin "2") (pinfunction "2_2") (pintype "passive"))
      (node (ref "R29") (pin "1") (pinfunction "1_1") (pintype "passive"))
      (node (ref "U9") (pin "8") (pinfunction "+_8") (pintype "input"))
    )
    (net (code "28") (name "Net-(U9A--)") (class "Default")
      (node (ref "R24") (pin "2") (pinfunction "2_2") (pintype "passive"))
      (node (ref "R25") (pin "1") (pinfunction "1_1") (pintype "passive"))
      (node (ref "U9") (pin "1") (pinfunction "-_1") (pintype "input"))
    )
    (net (code "29") (name "Net-(U9A-OUT+)") (class "Default")
      (node (ref "R25") (pin "2") (pinfunction "2_2") (pintype "passive"))
      (node (ref "R26") (pin "1") (pinfunction "1_1") (pintype "passive"))
      (node (ref "U9") (pin "4") (pinfunction "OUT+_4") (pintype "passive"))
    )
    (net (code "30") (name "Net-(U9A-OUT-)") (class "Default")
      (node (ref "R29") (pin "2") (pinfunction "2_2") (pintype "passive"))
      (node (ref "R30") (pin "1") (pinfunction "1_1") (pintype "passive"))
      (node (ref "U9") (pin "5") (pinfunction "OUT-_5") (pintype "passive"))
    )
    (net (code "31") (name "Net-(U11A--)") (class "Default")
      (node (ref "C37") (pin "2") (pinfunction "2_2") (pintype "passive"))
      (node (ref "U11") (pin "1") (pinfunction "OUT_1") (pintype "passive"))
      (node (ref "U11") (pin "2") (pinfunction "-_2") (pintype "passive"))
    )
    (net (code "32") (name "Net-(U11B-+)") (class "Default")
      (node (ref "C37") (pin "1") (pinfunction "1_1") (pintype "passive"))
      (node (ref "R28") (pin "1") (pinfunction "1_1") (pintype "passive"))
      (node (ref "U11") (pin "5") (pinfunction "+_5") (pintype "passive"))
    )
    (net (code "33") (name "Net-(U11B--)") (class "Default")
      (node (ref "C27") (pin "2") (pinfunction "2_2") (pintype "passive"))
      (node (ref "R22") (pin "2") (pinfunction "2_2") (pintype "passive"))
      (node (ref "R23") (pin "1") (pinfunction "1_1") (pintype "passive"))
      (node (ref "U11") (pin "6") (pinfunction "-_6") (pintype "passive"))
    )
    (net (code "34") (name "Net-(U11B-OUT)") (class "Default")
      (node (ref "C27") (pin "1") (pinfunction "1_1") (pintype "passive"))
      (node (ref "R23") (pin "2") (pinfunction "2_2") (pintype "passive"))
      (node (ref "R27") (pin "1") (pinfunction "1_1") (pintype "passive"))
      (node (ref "U11") (pin "7") (pinfunction "OUT_7") (pintype "passive"))
    )
    (net (code "35") (name "Net-(U12A-+)") (class "Default")
      (node (ref "C41") (pin "2") (pinfunction "2_2") (pintype "passive"))
      (node (ref "R31") (pin "2") (pinfunction "2_2") (pintype "passive"))
      (node (ref "R32") (pin "1") (pinfunction "1_1") (pintype "passive"))
      (node (ref "U12") (pin "3") (pinfunction "+_3") (pintype "passive"))
    )
    (net (code "36") (name "Net-(U12B--)") (class "Default")
      (node (ref "R31") (pin "1") (pinfunction "1_1") (pintype "passive"))
      (node (ref "U12") (pin "6") (pinfunction "-_6") (pintype "passive"))
      (node (ref "U12") (pin "7") (pinfunction "OUT_7") (pintype "passive"))
    )
    (net (code "37") (name "Net-(U14-1B)") (class "Default")
      (node (ref "R33") (pin "1") (pinfunction "1_1") (pintype "passive"))
      (node (ref "U14") (pin "7") (pinfunction "1B_7") (pintype "passive"))
    )
    (net (code "38") (name "Net-(U14-2B)") (class "Default")
      (node (ref "R34") (pin "1") (pinfunction "1_1") (pintype "passive"))
      (node (ref "U14") (pin "6") (pinfunction "2B_6") (pintype "passive"))
    )
    (net (code "39") (name "V_CM") (class "Default")
      (node (ref "R24") (pin "1") (pinfunction "1_1") (pintype "passive"))
      (node (ref "U12") (pin "1") (pinfunction "OUT_1") (pintype "passive"))
      (node (ref "U12") (pin "2") (pinfunction "-_2") (pintype "passive"))
      (node (ref "U9") (pin "2") (pinfunction "Vocm_2") (pintype "passive"))
    )
    (net (code "40") (name "X_CFSEL") (class "Default")
      (node (ref "Q2") (pin "1") (pinfunction "G_1") (pintype "passive"))
    )
    (net (code "41") (name "X_CLK") (class "Default")
      (node (ref "U14") (pin "2") (pinfunction "1A_2") (pintype "passive"))
    )
    (net (code "42") (name "X_RESET") (class "Default")
      (node (ref "U14") (pin "3") (pinfunction "2A_3") (pintype "passive"))
    )
    (net (code "43") (name "X_TRIG") (class "Default")
      (node (ref "U16") (pin "2") (pinfunction "1A_2") (pintype "passive"))
    )
    (net (code "44") (name "unconnected-(U9B-~{PD}-Pad7)") (class "Default")
      (node (ref "U9") (pin "7") (pinfunction "~{PD}_7") (pintype "input+no_connect"))
    )
    (net (code "45") (name "unconnected-(U13-VBM-Pad10)") (class "Default")
      (node (ref "U13") (pin "10") (pinfunction "VBM_10") (pintype "passive+no_connect"))
    )
    (net (code "46") (name "unconnected-(U15-VBM-Pad10)") (class "Default")
      (node (ref "U15") (pin "10") (pinfunction "VBM_10") (pintype "passive+no_connect"))
    )
    (net (code "47") (name "unconnected-(U16-2A-Pad3)") (class "Default")
      (node (ref "U16") (pin "3") (pinfunction "2A_3") (pintype "passive+no_connect"))
    )
  )
)
